# Transmitter.net
KiCad netlist of a schematic drawn in Altium Designer
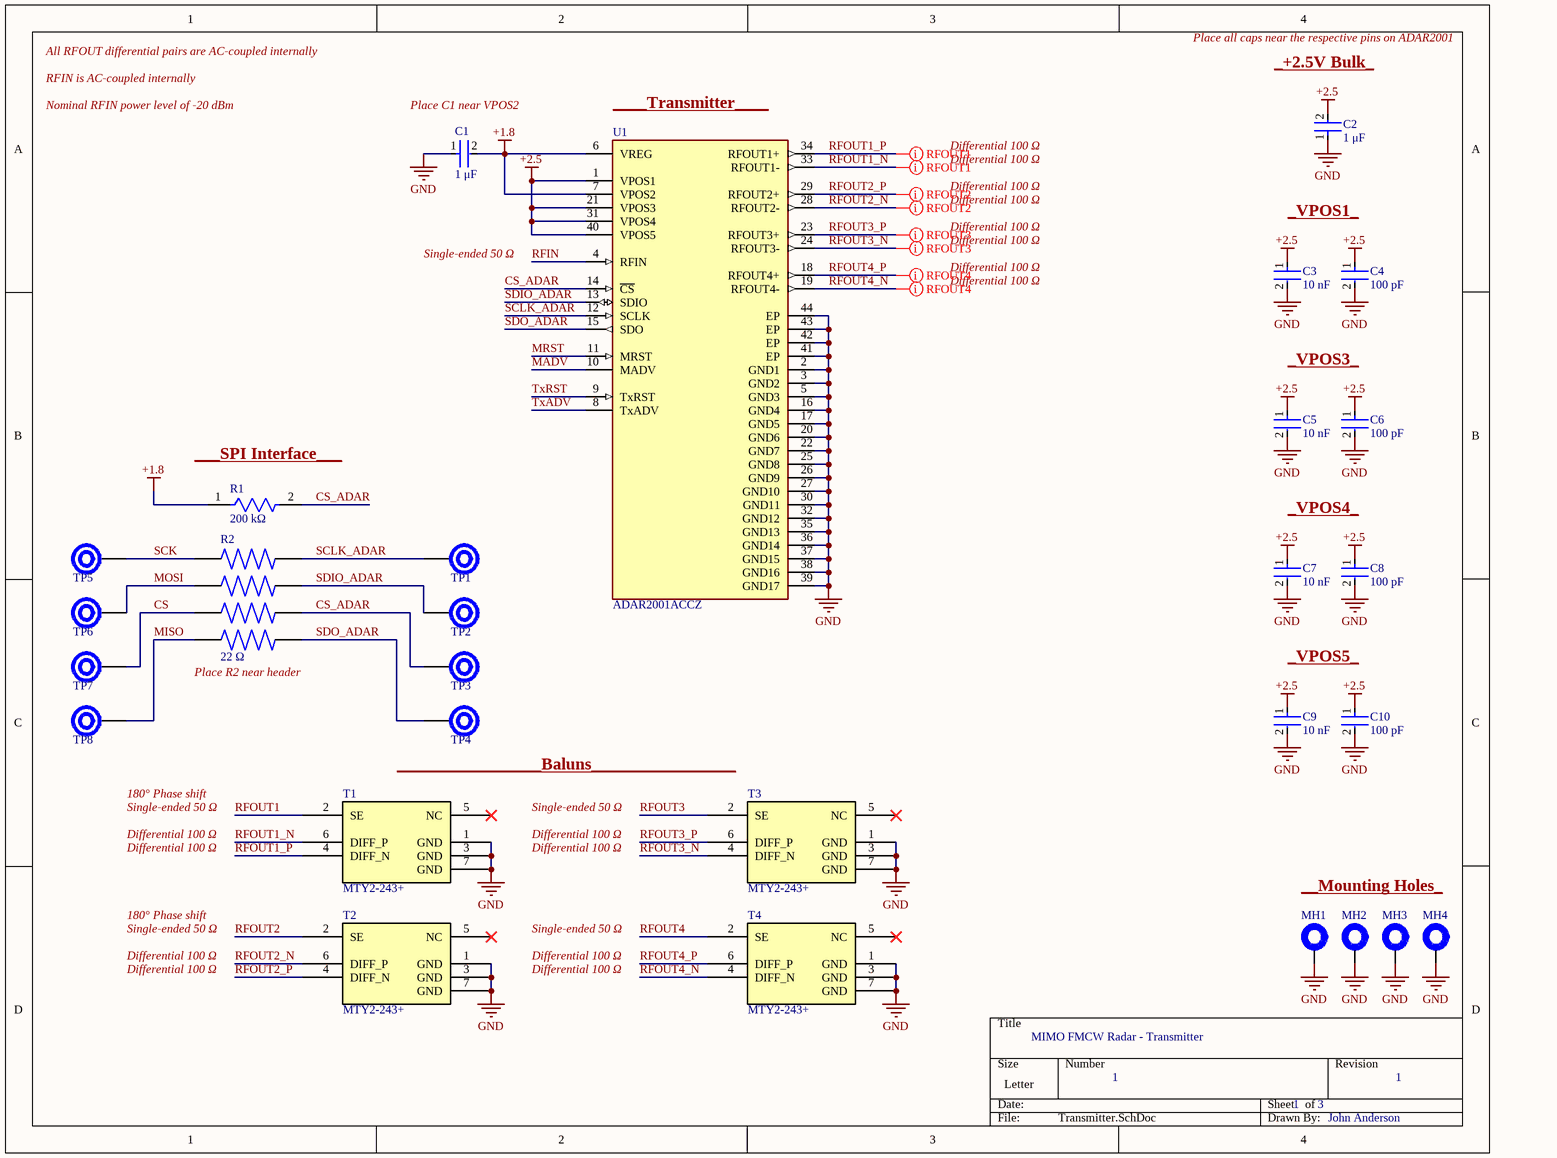
[diagram p0: Transmitter.SchDoc]

(export (version "E")
  (design (tool "Eeschema 10.0.6"))
  (components
    (comp (ref "C1")
      (value "1 μF")
      (footprint "FP-0603-L_1_6_0_15-W_0_8-MFG")
      (libsource (lib "Power Pullers") (part "11868f565c42a9108669ba33697ecf6"))
    )
    (comp (ref "C2")
      (value "1 μF")
      (footprint "FP-0603-L_1_6_0_15-W_0_8-MFG")
      (libsource (lib "Power Pullers") (part "11868f565c42a9108669ba33697ecf6"))
    )
    (comp (ref "C3")
      (value "10 nF")
      (footprint "CGA3E2X7R1H103K080AA-Footprint-1")
      (description "CGA Series 0603 10 nF 50 V ±10 % Tolerance X7R SMT Multilayer Ceramic Capacitor")
      (fields (field (name "TOLERANCE") "10%"))
      (libsource (lib "Power Pullers") (part "CGA3E2X7R1H103K080AA-Symbol-1"))
    )
    (comp (ref "C4")
      (value "100 pF")
      (footprint "FP-C0603C-CF-IPC_C")
      (description "Multilayer Ceramic Capacitors MLCC – SMD/SMT; KEMET; C0603C101J5GACTU; 100 pF; 0603; 50 V; 50 V")
      (fields (field (name "VOLTAGE") "50V") (field (name "TOLERANCE") "5%"))
      (libsource (lib "Power Pullers") (part "b4654b650e69147ec39a6b967a45e02"))
    )
    (comp (ref "C5")
      (value "10 nF")
      (footprint "CGA3E2X7R1H103K080AA-Footprint-1")
      (description "CGA Series 0603 10 nF 50 V ±10 % Tolerance X7R SMT Multilayer Ceramic Capacitor")
      (fields (field (name "TOLERANCE") "10%"))
      (libsource (lib "Power Pullers") (part "CGA3E2X7R1H103K080AA-Symbol-1"))
    )
    (comp (ref "C6")
      (value "100 pF")
      (footprint "FP-C0603C-CF-IPC_C")
      (description "Multilayer Ceramic Capacitors MLCC – SMD/SMT; KEMET; C0603C101J5GACTU; 100 pF; 0603; 50 V; 50 V")
      (fields (field (name "VOLTAGE") "50V") (field (name "TOLERANCE") "5%"))
      (libsource (lib "Power Pullers") (part "b4654b650e69147ec39a6b967a45e02"))
    )
    (comp (ref "C7")
      (value "10 nF")
      (footprint "CGA3E2X7R1H103K080AA-Footprint-1")
      (description "CGA Series 0603 10 nF 50 V ±10 % Tolerance X7R SMT Multilayer Ceramic Capacitor")
      (fields (field (name "TOLERANCE") "10%"))
      (libsource (lib "Power Pullers") (part "CGA3E2X7R1H103K080AA-Symbol-1"))
    )
    (comp (ref "C8")
      (value "100 pF")
      (footprint "FP-C0603C-CF-IPC_C")
      (description "Multilayer Ceramic Capacitors MLCC – SMD/SMT; KEMET; C0603C101J5GACTU; 100 pF; 0603; 50 V; 50 V")
      (fields (field (name "VOLTAGE") "50V") (field (name "TOLERANCE") "5%"))
      (libsource (lib "Power Pullers") (part "b4654b650e69147ec39a6b967a45e02"))
    )
    (comp (ref "C9")
      (value "10 nF")
      (footprint "CGA3E2X7R1H103K080AA-Footprint-1")
      (description "CGA Series 0603 10 nF 50 V ±10 % Tolerance X7R SMT Multilayer Ceramic Capacitor")
      (fields (field (name "TOLERANCE") "10%"))
      (libsource (lib "Power Pullers") (part "CGA3E2X7R1H103K080AA-Symbol-1"))
    )
    (comp (ref "C10")
      (value "100 pF")
      (footprint "FP-C0603C-CF-IPC_C")
      (description "Multilayer Ceramic Capacitors MLCC – SMD/SMT; KEMET; C0603C101J5GACTU; 100 pF; 0603; 50 V; 50 V")
      (fields (field (name "VOLTAGE") "50V") (field (name "TOLERANCE") "5%"))
      (libsource (lib "Power Pullers") (part "b4654b650e69147ec39a6b967a45e02"))
    )
    (comp (ref "MH1")
      (value "M3 Plated Mounting Hole - Loose")
      (footprint "M3 Plated Mounting Hole-Footprint-1")
      (description "Plated M3 mounting hole with loose tolerance. 3.6 mm hole diameter, 4.6 mm plated diameter.")
      (libsource (lib "Power Pullers") (part "M3 Plated Mounting Hole-Symbol-1"))
    )
    (comp (ref "MH2")
      (value "M3 Plated Mounting Hole - Loose")
      (footprint "M3 Plated Mounting Hole-Footprint-1")
      (description "Plated M3 mounting hole with loose tolerance. 3.6 mm hole diameter, 4.6 mm plated diameter.")
      (libsource (lib "Power Pullers") (part "M3 Plated Mounting Hole-Symbol-1"))
    )
    (comp (ref "MH3")
      (value "M3 Plated Mounting Hole - Loose")
      (footprint "M3 Plated Mounting Hole-Footprint-1")
      (description "Plated M3 mounting hole with loose tolerance. 3.6 mm hole diameter, 4.6 mm plated diameter.")
      (libsource (lib "Power Pullers") (part "M3 Plated Mounting Hole-Symbol-1"))
    )
    (comp (ref "MH4")
      (value "M3 Plated Mounting Hole - Loose")
      (footprint "M3 Plated Mounting Hole-Footprint-1")
      (description "Plated M3 mounting hole with loose tolerance. 3.6 mm hole diameter, 4.6 mm plated diameter.")
      (libsource (lib "Power Pullers") (part "M3 Plated Mounting Hole-Symbol-1"))
    )
    (comp (ref "R1")
      (value "200 kΩ")
      (footprint "FP-RG1608-IPC_C")
      (description "Res Thin Film 0603 200K Ohm 0.1% 0.1W(1/10W) ±25ppm/C Sulfur Resistant Pad SMD Automotive T/R")
      (fields (field (name "TOLERANCE") "0.1%"))
      (libsource (lib "Power Pullers") (part "1029c3af85768c4190bb7ad29bc67b5"))
    )
    (comp (ref "R2")
      (value "22 Ω")
      (footprint "CAY16-22R0F4LF-Footprint-1")
      (description "Res Thick Film Array 22 Ohm 1% 0.25W(1/4W) ±200ppm/C ISOL 8-Pin 1206(4 X 0603) Convex SMD T/R")
      (fields (field (name "TOLERANCE") "1%"))
      (libsource (lib "Power Pullers") (part "CAY16-22R0F4LF-Symbol-1"))
    )
    (comp (ref "T1")
      (value "MTY2-243+")
      (footprint "MTY2-243+-Footprint-1")
      (description "RF Transformer, 10000MHz Min, 24000MHz Max")
      (libsource (lib "Power Pullers") (part "MTY2-243+-Symbol-1"))
    )
    (comp (ref "T2")
      (value "MTY2-243+")
      (footprint "MTY2-243+-Footprint-1")
      (description "RF Transformer, 10000MHz Min, 24000MHz Max")
      (libsource (lib "Power Pullers") (part "MTY2-243+-Symbol-1"))
    )
    (comp (ref "T3")
      (value "MTY2-243+")
      (footprint "MTY2-243+-Footprint-1")
      (description "RF Transformer, 10000MHz Min, 24000MHz Max")
      (libsource (lib "Power Pullers") (part "MTY2-243+-Symbol-1"))
    )
    (comp (ref "T4")
      (value "MTY2-243+")
      (footprint "MTY2-243+-Footprint-1")
      (description "RF Transformer, 10000MHz Min, 24000MHz Max")
      (libsource (lib "Power Pullers") (part "MTY2-243+-Symbol-1"))
    )
    (comp (ref "TP1")
      (value "Test Point - 32 mil")
      (footprint "Test Point - 32 mil-Footprint-1")
      (description "32 mil (0.8 mm) test point.")
      (libsource (lib "Power Pullers") (part "Test Point - 32 mil-Symbol-1"))
    )
    (comp (ref "TP2")
      (value "Test Point - 32 mil")
      (footprint "Test Point - 32 mil-Footprint-1")
      (description "32 mil (0.8 mm) test point.")
      (libsource (lib "Power Pullers") (part "Test Point - 32 mil-Symbol-1"))
    )
    (comp (ref "TP3")
      (value "Test Point - 32 mil")
      (footprint "Test Point - 32 mil-Footprint-1")
      (description "32 mil (0.8 mm) test point.")
      (libsource (lib "Power Pullers") (part "Test Point - 32 mil-Symbol-1"))
    )
    (comp (ref "TP4")
      (value "Test Point - 32 mil")
      (footprint "Test Point - 32 mil-Footprint-1")
      (description "32 mil (0.8 mm) test point.")
      (libsource (lib "Power Pullers") (part "Test Point - 32 mil-Symbol-1"))
    )
    (comp (ref "TP5")
      (value "Test Point - 32 mil")
      (footprint "Test Point - 32 mil-Footprint-1")
      (description "32 mil (0.8 mm) test point.")
      (libsource (lib "Power Pullers") (part "Test Point - 32 mil-Symbol-1"))
    )
    (comp (ref "TP6")
      (value "Test Point - 32 mil")
      (footprint "Test Point - 32 mil-Footprint-1")
      (description "32 mil (0.8 mm) test point.")
      (libsource (lib "Power Pullers") (part "Test Point - 32 mil-Symbol-1"))
    )
    (comp (ref "TP7")
      (value "Test Point - 32 mil")
      (footprint "Test Point - 32 mil-Footprint-1")
      (description "32 mil (0.8 mm) test point.")
      (libsource (lib "Power Pullers") (part "Test Point - 32 mil-Symbol-1"))
    )
    (comp (ref "TP8")
      (value "Test Point - 32 mil")
      (footprint "Test Point - 32 mil-Footprint-1")
      (description "32 mil (0.8 mm) test point.")
      (libsource (lib "Power Pullers") (part "Test Point - 32 mil-Symbol-1"))
    )
    (comp (ref "U1")
      (value "ADAR2001ACCZ")
      (footprint "FP-CC-40-7-MFG")
      (description "Active RF Multipliers x4 10GHz to 40GHz-OUT 40-Pin LGA EP Tray")
      (libsource (lib "Power Pullers") (part "77d4f6b30536364c10e10071c59ab92"))
    )
  )
  (nets
    (net (code "1") (name "+1.8") (class "Default")
      (node (ref "C1") (pin "2") (pinfunction "2_2") (pintype "passive"))
      (node (ref "R1") (pin "1") (pinfunction "1_1") (pintype "passive"))
      (node (ref "U1") (pin "6") (pinfunction "VREG_6") (pintype "power_in"))
      (node (ref "U1") (pin "7") (pinfunction "VPOS2_7") (pintype "power_in"))
    )
    (net (code "2") (name "+2.5") (class "Default")
      (node (ref "C10") (pin "1") (pinfunction "1_1") (pintype "passive"))
      (node (ref "C2") (pin "2") (pinfunction "2_2") (pintype "passive"))
      (node (ref "C3") (pin "1") (pinfunction "1_1") (pintype "passive"))
      (node (ref "C4") (pin "1") (pinfunction "1_1") (pintype "passive"))
      (node (ref "C5") (pin "1") (pinfunction "1_1") (pintype "passive"))
      (node (ref "C6") (pin "1") (pinfunction "1_1") (pintype "passive"))
      (node (ref "C7") (pin "1") (pinfunction "1_1") (pintype "passive"))
      (node (ref "C8") (pin "1") (pinfunction "1_1") (pintype "passive"))
      (node (ref "C9") (pin "1") (pinfunction "1_1") (pintype "passive"))
      (node (ref "U1") (pin "1") (pinfunction "VPOS1_1") (pintype "power_in"))
      (node (ref "U1") (pin "21") (pinfunction "VPOS3_21") (pintype "power_in"))
      (node (ref "U1") (pin "31") (pinfunction "VPOS4_31") (pintype "power_in"))
      (node (ref "U1") (pin "40") (pinfunction "VPOS5_40") (pintype "power_in"))
    )
    (net (code "3") (name "/CS") (class "Default")
      (node (ref "R2") (pin "3") (pinfunction "3_3") (pintype "passive"))
      (node (ref "TP7") (pin "1") (pinfunction "1_1") (pintype "passive"))
    )
    (net (code "4") (name "/CS_ADAR") (class "Default")
      (node (ref "R1") (pin "2") (pinfunction "2_2") (pintype "passive"))
      (node (ref "R2") (pin "6") (pinfunction "6_6") (pintype "passive"))
      (node (ref "TP3") (pin "1") (pinfunction "1_1") (pintype "passive"))
      (node (ref "U1") (pin "14") (pinfunction "~{CS}_14") (pintype "input"))
    )
    (net (code "5") (name "/MADV") (class "Default")
      (node (ref "U1") (pin "10") (pinfunction "MADV_10") (pintype "passive"))
    )
    (net (code "6") (name "/MISO") (class "Default")
      (node (ref "R2") (pin "4") (pinfunction "4_4") (pintype "passive"))
      (node (ref "TP8") (pin "1") (pinfunction "1_1") (pintype "passive"))
    )
    (net (code "7") (name "/MOSI") (class "Default")
      (node (ref "R2") (pin "2") (pinfunction "2_2") (pintype "passive"))
      (node (ref "TP6") (pin "1") (pinfunction "1_1") (pintype "passive"))
    )
    (net (code "8") (name "/MRST") (class "Default")
      (node (ref "U1") (pin "11") (pinfunction "MRST_11") (pintype "input"))
    )
    (net (code "9") (name "/RFIN") (class "Default")
      (node (ref "U1") (pin "4") (pinfunction "RFIN_4") (pintype "input"))
    )
    (net (code "10") (name "/RFOUT1") (class "Default")
      (node (ref "T1") (pin "2") (pinfunction "SE_2") (pintype "passive"))
    )
    (net (code "11") (name "/RFOUT1_N") (class "Default")
      (node (ref "T1") (pin "6") (pinfunction "DIFF_P_6") (pintype "passive"))
      (node (ref "U1") (pin "33") (pinfunction "RFOUT1-_33") (pintype "output"))
    )
    (net (code "12") (name "/RFOUT1_P") (class "Default")
      (node (ref "T1") (pin "4") (pinfunction "DIFF_N_4") (pintype "passive"))
      (node (ref "U1") (pin "34") (pinfunction "RFOUT1+_34") (pintype "output"))
    )
    (net (code "13") (name "/RFOUT2") (class "Default")
      (node (ref "T2") (pin "2") (pinfunction "SE_2") (pintype "passive"))
    )
    (net (code "14") (name "/RFOUT2_N") (class "Default")
      (node (ref "T2") (pin "6") (pinfunction "DIFF_P_6") (pintype "passive"))
      (node (ref "U1") (pin "28") (pinfunction "RFOUT2-_28") (pintype "output"))
    )
    (net (code "15") (name "/RFOUT2_P") (class "Default")
      (node (ref "T2") (pin "4") (pinfunction "DIFF_N_4") (pintype "passive"))
      (node (ref "U1") (pin "29") (pinfunction "RFOUT2+_29") (pintype "output"))
    )
    (net (code "16") (name "/RFOUT3") (class "Default")
      (node (ref "T3") (pin "2") (pinfunction "SE_2") (pintype "passive"))
    )
    (net (code "17") (name "/RFOUT3_N") (class "Default")
      (node (ref "T3") (pin "4") (pinfunction "DIFF_N_4") (pintype "passive"))
      (node (ref "U1") (pin "24") (pinfunction "RFOUT3-_24") (pintype "output"))
    )
    (net (code "18") (name "/RFOUT3_P") (class "Default")
      (node (ref "T3") (pin "6") (pinfunction "DIFF_P_6") (pintype "passive"))
      (node (ref "U1") (pin "23") (pinfunction "RFOUT3+_23") (pintype "output"))
    )
    (net (code "19") (name "/RFOUT4") (class "Default")
      (node (ref "T4") (pin "2") (pinfunction "SE_2") (pintype "passive"))
    )
    (net (code "20") (name "/RFOUT4_N") (class "Default")
      (node (ref "T4") (pin "4") (pinfunction "DIFF_N_4") (pintype "passive"))
      (node (ref "U1") (pin "19") (pinfunction "RFOUT4-_19") (pintype "output"))
    )
    (net (code "21") (name "/RFOUT4_P") (class "Default")
      (node (ref "T4") (pin "6") (pinfunction "DIFF_P_6") (pintype "passive"))
      (node (ref "U1") (pin "18") (pinfunction "RFOUT4+_18") (pintype "output"))
    )
    (net (code "22") (name "/SCK") (class "Default")
      (node (ref "R2") (pin "1") (pinfunction "1_1") (pintype "passive"))
      (node (ref "TP5") (pin "1") (pinfunction "1_1") (pintype "passive"))
    )
    (net (code "23") (name "/SCLK_ADAR") (class "Default")
      (node (ref "R2") (pin "8") (pinfunction "8_8") (pintype "passive"))
      (node (ref "TP1") (pin "1") (pinfunction "1_1") (pintype "passive"))
      (node (ref "U1") (pin "12") (pinfunction "SCLK_12") (pintype "input"))
    )
    (net (code "24") (name "/SDIO_ADAR") (class "Default")
      (node (ref "R2") (pin "7") (pinfunction "7_7") (pintype "passive"))
      (node (ref "TP2") (pin "1") (pinfunction "1_1") (pintype "passive"))
      (node (ref "U1") (pin "13") (pinfunction "SDIO_13") (pintype "bidirectional"))
    )
    (net (code "25") (name "/SDO_ADAR") (class "Default")
      (node (ref "R2") (pin "5") (pinfunction "5_5") (pintype "passive"))
      (node (ref "TP4") (pin "1") (pinfunction "1_1") (pintype "passive"))
      (node (ref "U1") (pin "15") (pinfunction "SDO_15") (pintype "output"))
    )
    (net (code "26") (name "/TxADV") (class "Default")
      (node (ref "U1") (pin "8") (pinfunction "TxADV_8") (pintype "passive"))
    )
    (net (code "27") (name "/TxRST") (class "Default")
      (node (ref "U1") (pin "9") (pinfunction "TxRST_9") (pintype "input"))
    )
    (net (code "28") (name "GND") (class "Default")
      (node (ref "C1") (pin "1") (pinfunction "1_1") (pintype "passive"))
      (node (ref "C10") (pin "2") (pinfunction "2_2") (pintype "passive"))
      (node (ref "C2") (pin "1") (pinfunction "1_1") (pintype "passive"))
      (node (ref "C3") (pin "2") (pinfunction "2_2") (pintype "passive"))
      (node (ref "C4") (pin "2") (pinfunction "2_2") (pintype "passive"))
      (node (ref "C5") (pin "2") (pinfunction "2_2") (pintype "passive"))
      (node (ref "C6") (pin "2") (pinfunction "2_2") (pintype "passive"))
      (node (ref "C7") (pin "2") (pinfunction "2_2") (pintype "passive"))
      (node (ref "C8") (pin "2") (pinfunction "2_2") (pintype "passive"))
      (node (ref "C9") (pin "2") (pinfunction "2_2") (pintype "passive"))
      (node (ref "MH1") (pin "1") (pinfunction "1_1") (pintype "passive"))
      (node (ref "MH2") (pin "1") (pinfunction "1_1") (pintype "passive"))
      (node (ref "MH3") (pin "1") (pinfunction "1_1") (pintype "passive"))
      (node (ref "MH4") (pin "1") (pinfunction "1_1") (pintype "passive"))
      (node (ref "T1") (pin "1") (pinfunction "GND_1") (pintype "power_in"))
      (node (ref "T1") (pin "3") (pinfunction "GND_3") (pintype "power_in"))
      (node (ref "T1") (pin "7") (pinfunction "GND_7") (pintype "power_in"))
      (node (ref "T2") (pin "1") (pinfunction "GND_1") (pintype "power_in"))
      (node (ref "T2") (pin "3") (pinfunction "GND_3") (pintype "power_in"))
      (node (ref "T2") (pin "7") (pinfunction "GND_7") (pintype "power_in"))
      (node (ref "T3") (pin "1") (pinfunction "GND_1") (pintype "power_in"))
      (node (ref "T3") (pin "3") (pinfunction "GND_3") (pintype "power_in"))
      (node (ref "T3") (pin "7") (pinfunction "GND_7") (pintype "power_in"))
      (node (ref "T4") (pin "1") (pinfunction "GND_1") (pintype "power_in"))
      (node (ref "T4") (pin "3") (pinfunction "GND_3") (pintype "power_in"))
      (node (ref "T4") (pin "7") (pinfunction "GND_7") (pintype "power_in"))
      (node (ref "U1") (pin "16") (pinfunction "GND4_16") (pintype "power_in"))
      (node (ref "U1") (pin "17") (pinfunction "GND5_17") (pintype "power_in"))
      (node (ref "U1") (pin "2") (pinfunction "GND1_2") (pintype "power_in"))
      (node (ref "U1") (pin "20") (pinfunction "GND6_20") (pintype "power_in"))
      (node (ref "U1") (pin "22") (pinfunction "GND7_22") (pintype "power_in"))
      (node (ref "U1") (pin "25") (pinfunction "GND8_25") (pintype "power_in"))
      (node (ref "U1") (pin "26") (pinfunction "GND9_26") (pintype "power_in"))
      (node (ref "U1") (pin "27") (pinfunction "GND10_27") (pintype "power_in"))
      (node (ref "U1") (pin "3") (pinfunction "GND2_3") (pintype "power_in"))
      (node (ref "U1") (pin "30") (pinfunction "GND11_30") (pintype "power_in"))
      (node (ref "U1") (pin "32") (pinfunction "GND12_32") (pintype "power_in"))
      (node (ref "U1") (pin "35") (pinfunction "GND13_35") (pintype "power_in"))
      (node (ref "U1") (pin "36") (pinfunction "GND14_36") (pintype "power_in"))
      (node (ref "U1") (pin "37") (pinfunction "GND15_37") (pintype "power_in"))
      (node (ref "U1") (pin "38") (pinfunction "GND16_38") (pintype "power_in"))
      (node (ref "U1") (pin "39") (pinfunction "GND17_39") (pintype "power_in"))
      (node (ref "U1") (pin "41") (pinfunction "EP_41") (pintype "passive"))
      (node (ref "U1") (pin "42") (pinfunction "EP_42") (pintype "passive"))
      (node (ref "U1") (pin "43") (pinfunction "EP_43") (pintype "passive"))
      (node (ref "U1") (pin "44") (pinfunction "EP_44") (pintype "passive"))
      (node (ref "U1") (pin "5") (pinfunction "GND3_5") (pintype "power_in"))
    )
    (net (code "29") (name "unconnected-(T1-NC-Pad5)") (class "Default")
      (node (ref "T1") (pin "5") (pinfunction "NC_5") (pintype "passive+no_connect"))
    )
    (net (code "30") (name "unconnected-(T2-NC-Pad5)") (class "Default")
      (node (ref "T2") (pin "5") (pinfunction "NC_5") (pintype "passive+no_connect"))
    )
    (net (code "31") (name "unconnected-(T3-NC-Pad5)") (class "Default")
      (node (ref "T3") (pin "5") (pinfunction "NC_5") (pintype "passive+no_connect"))
    )
    (net (code "32") (name "unconnected-(T4-NC-Pad5)") (class "Default")
      (node (ref "T4") (pin "5") (pinfunction "NC_5") (pintype "passive+no_connect"))
    )
  )
)
